# STM32H743.net
KiCad netlist of a schematic drawn in Altium Designer
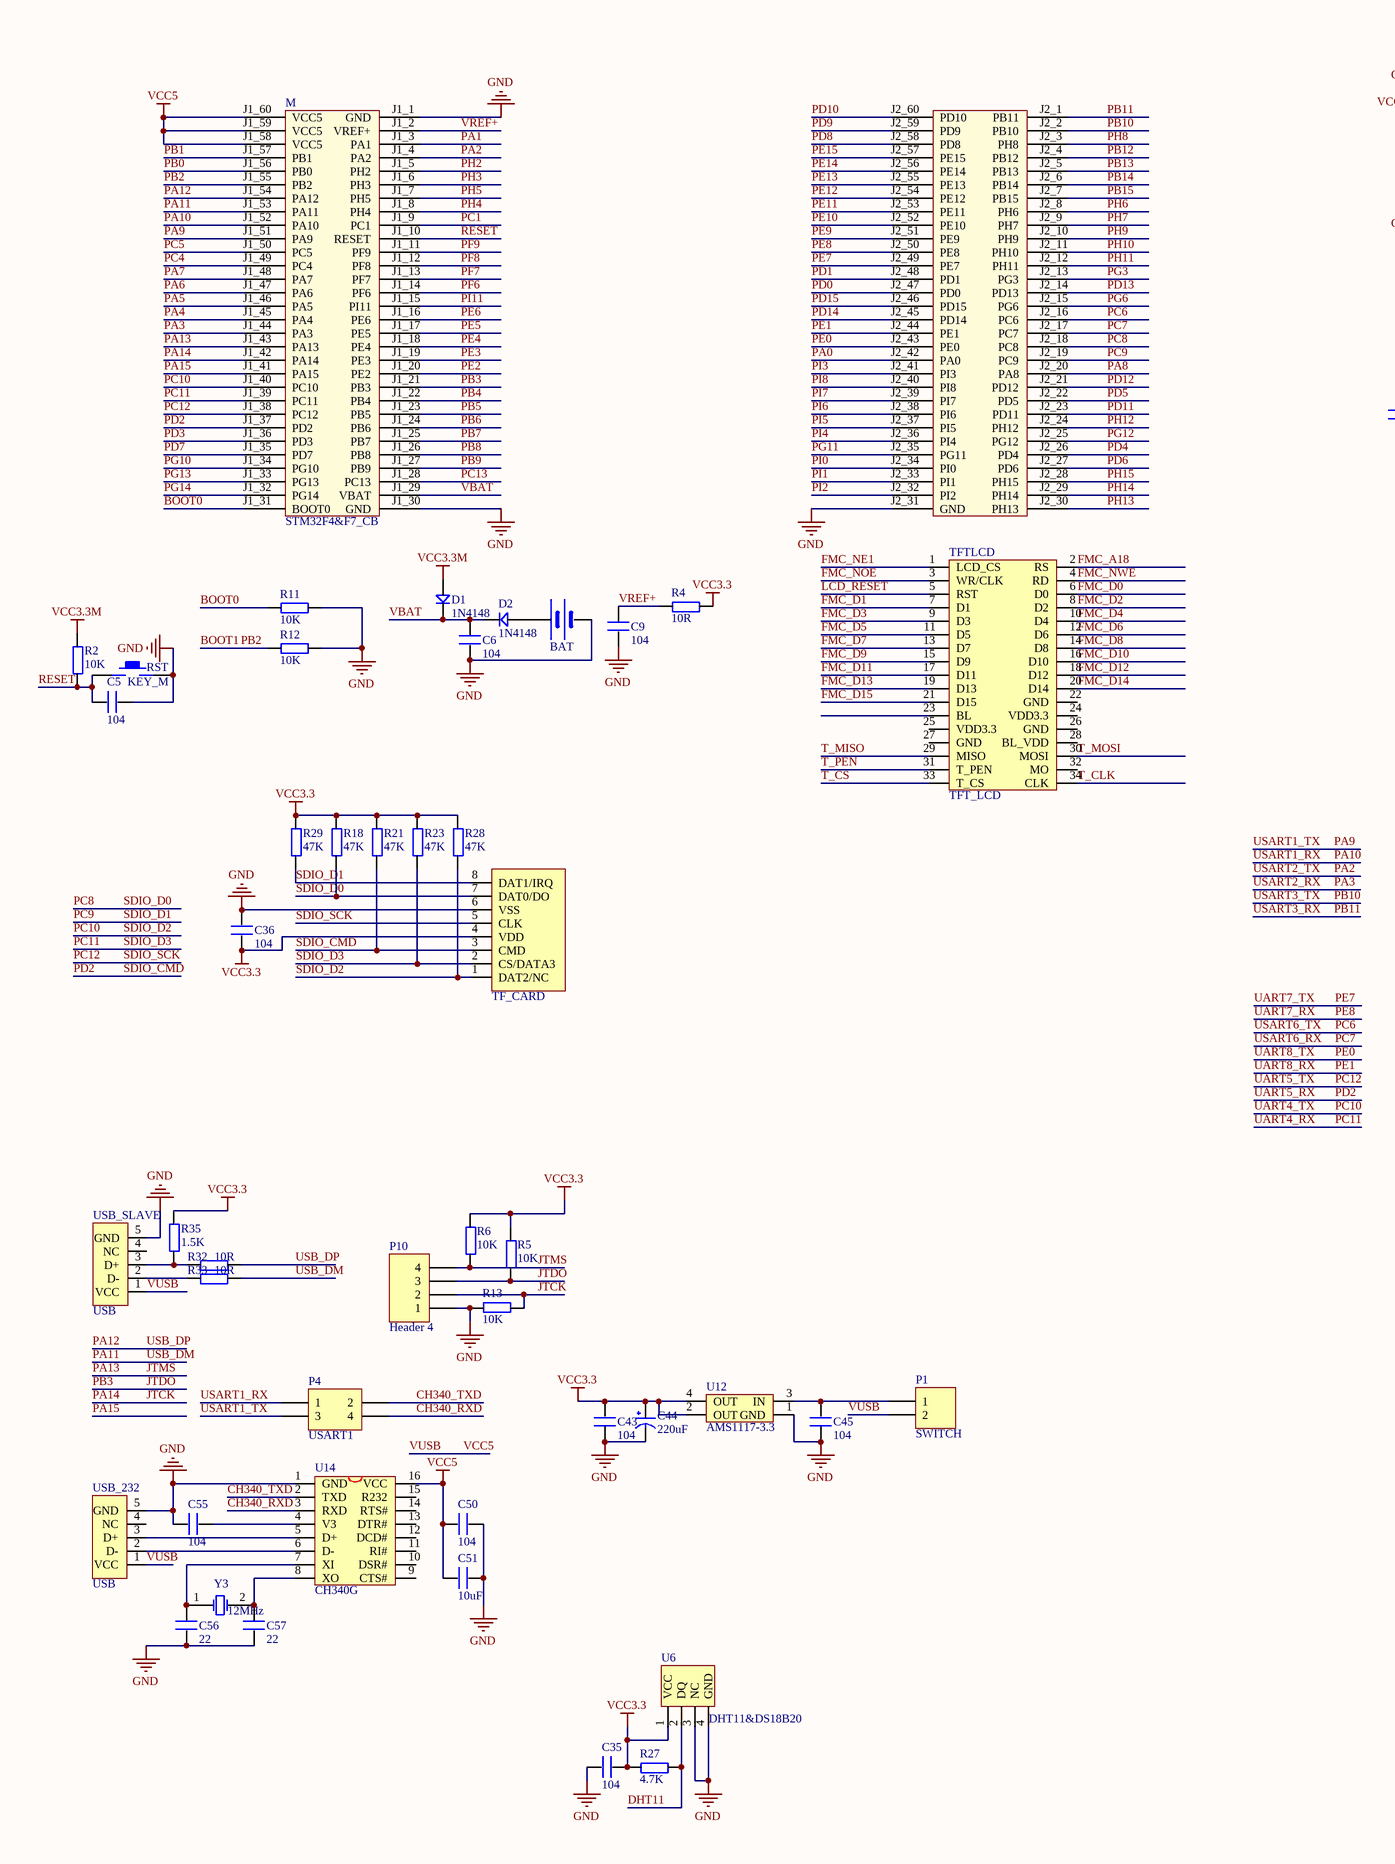
[diagram p0: STM32H743.SchDoc, left]
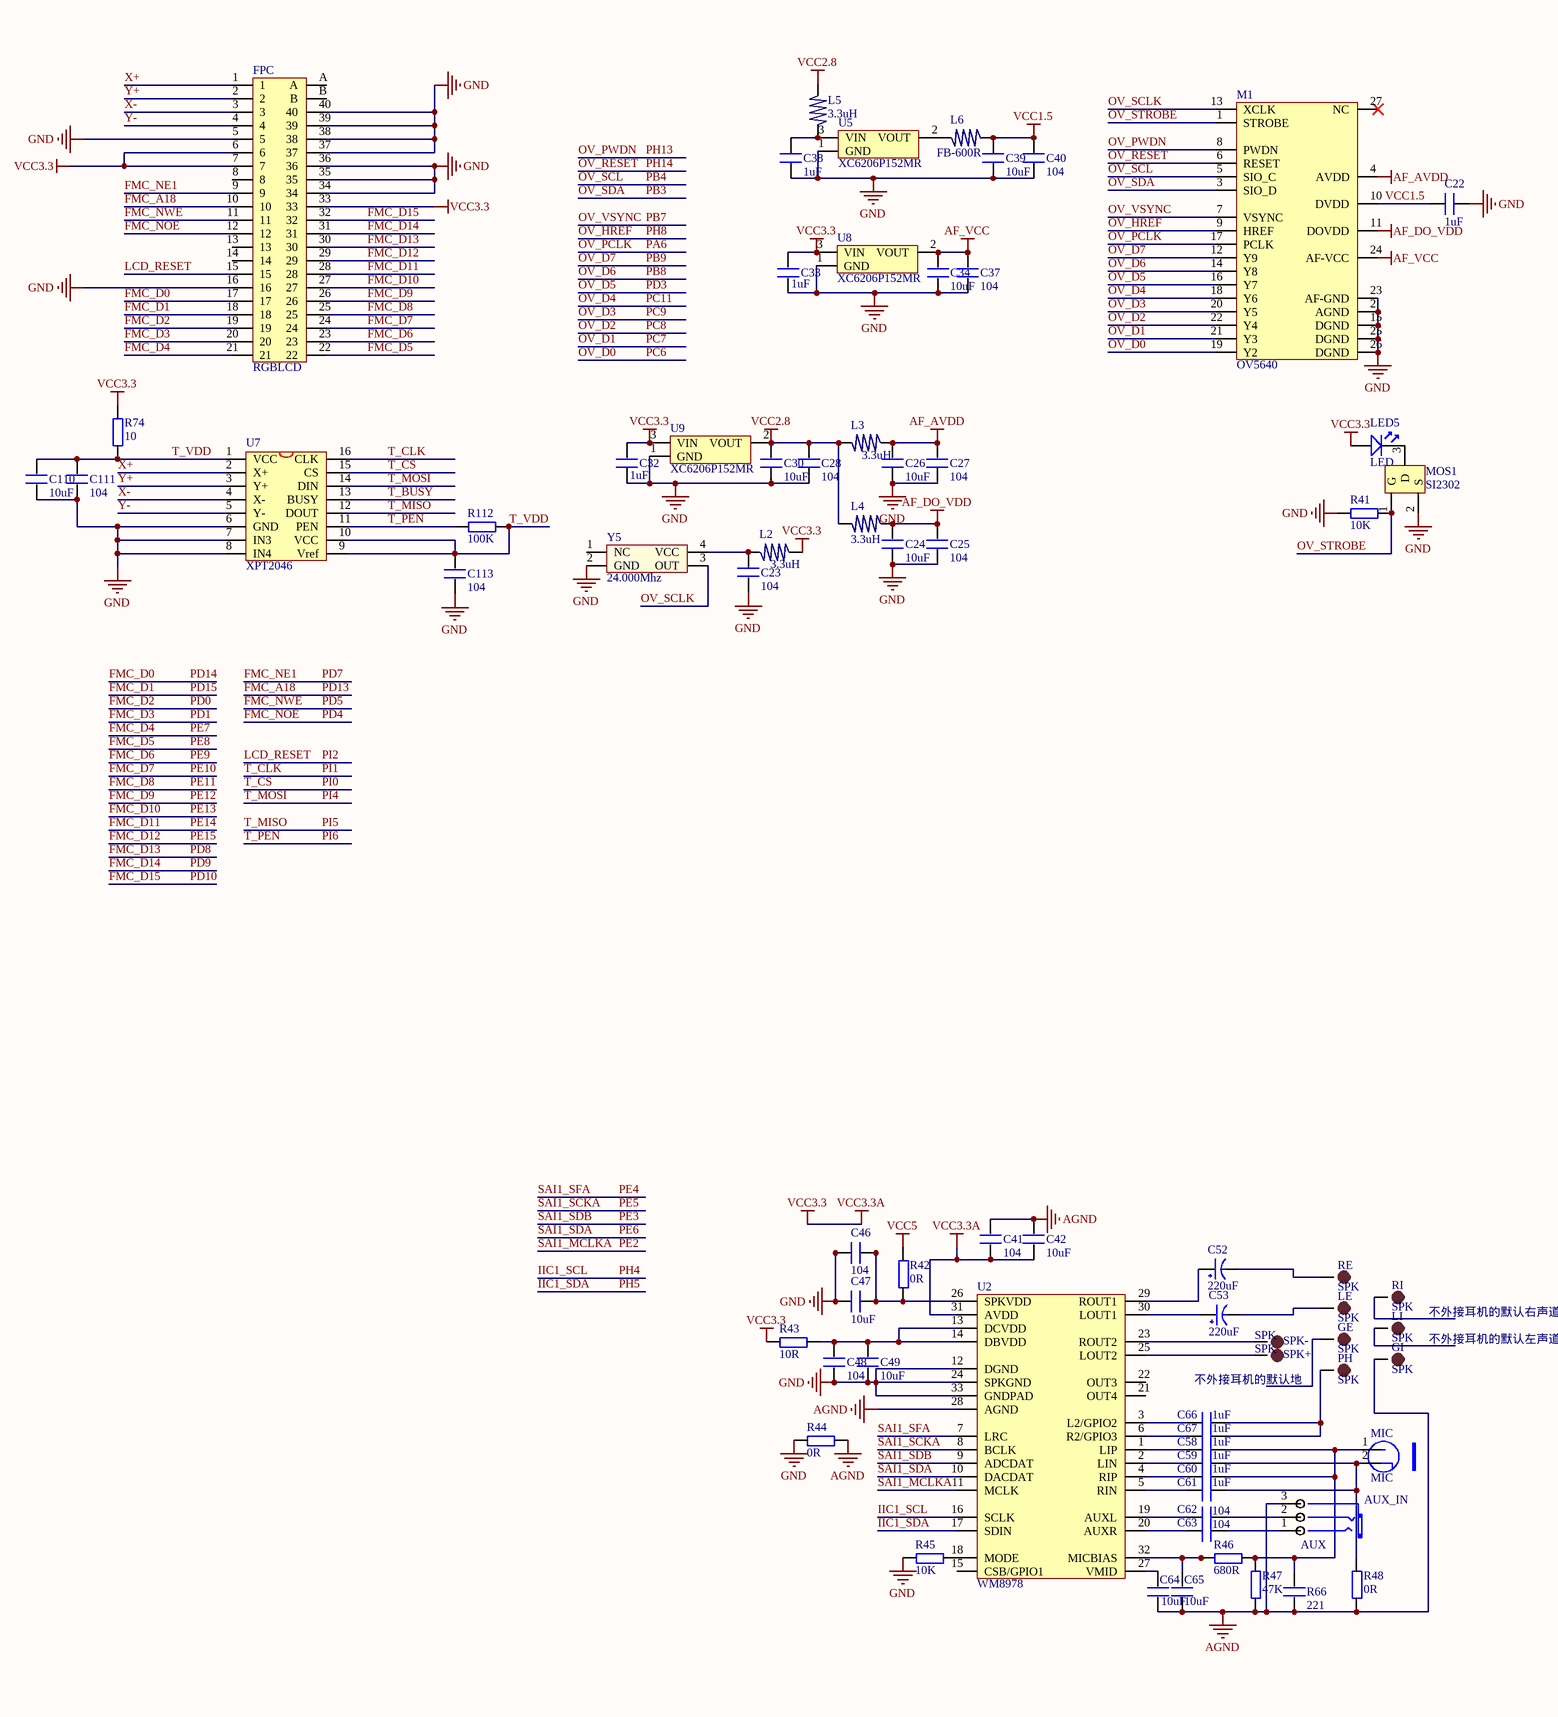
[diagram p1: STM32H743.SchDoc, right]

(export (version "E")
  (design (tool "Eeschema 10.0.6"))
  (components
    (comp (ref "AUX_IN")
      (value "AUX")
      (footprint "PHONE_ST")
      (libsource (lib "阿波罗STM32F4&F7底板封装库") (part "PHONE_M"))
    )
    (comp (ref "BAT")
      (value "BATT")
      (footprint "CR1220_A")
      (libsource (lib "WarShip V3 STM32103封装库") (part "BAT"))
    )
    (comp (ref "C5")
      (value "104")
      (footprint "C 0603_M")
      (libsource (lib "WarShip V3 STM32103封装库") (part "C"))
    )
    (comp (ref "C6")
      (value "104")
      (footprint "C 0603_M")
      (libsource (lib "WarShip V3 STM32103封装库") (part "C"))
    )
    (comp (ref "C9")
      (value "104")
      (footprint "C 0603_M")
      (libsource (lib "WarShip V3 STM32103封装库") (part "C"))
    )
    (comp (ref "C22") (value "1uF") (footprint "C 0603_M") (libsource (lib "ATK-OV5640摄像头模块封装库") (part "C")))
    (comp (ref "C23") (value "104") (footprint "C 0603_M") (libsource (lib "ATK-OV5640摄像头模块封装库") (part "C")))
    (comp (ref "C24") (value "10uF") (footprint "C 0603_M") (libsource (lib "ATK-OV5640摄像头模块封装库") (part "C")))
    (comp (ref "C25") (value "104") (footprint "C 0603_M") (libsource (lib "ATK-OV5640摄像头模块封装库") (part "C")))
    (comp (ref "C26") (value "10uF") (footprint "C 0603_M") (libsource (lib "ATK-OV5640摄像头模块封装库") (part "C")))
    (comp (ref "C27") (value "104") (footprint "C 0603_M") (libsource (lib "ATK-OV5640摄像头模块封装库") (part "C")))
    (comp (ref "C28") (value "104") (footprint "C 0603_M") (libsource (lib "ATK-OV5640摄像头模块封装库") (part "C")))
    (comp (ref "C30") (value "10uF") (footprint "C 0603_M") (libsource (lib "ATK-OV5640摄像头模块封装库") (part "C")))
    (comp (ref "C32") (value "1uF") (footprint "C 0603_M") (libsource (lib "ATK-OV5640摄像头模块封装库") (part "C")))
    (comp (ref "C33") (value "1uF") (footprint "C 0603_M") (libsource (lib "ATK-OV5640摄像头模块封装库") (part "C")))
    (comp (ref "C34") (value "10uF") (footprint "C 0603_M") (libsource (lib "ATK-OV5640摄像头模块封装库") (part "C")))
    (comp (ref "C35")
      (value "104")
      (footprint "C 0603_M")
      (libsource (lib "WarShip V3 STM32103封装库") (part "C"))
    )
    (comp (ref "C36")
      (value "104")
      (footprint "C 0603_M")
      (libsource (lib "WarShip V3 STM32103封装库") (part "C"))
    )
    (comp (ref "C37") (value "104") (footprint "C 0603_M") (libsource (lib "ATK-OV5640摄像头模块封装库") (part "C")))
    (comp (ref "C38") (value "1uF") (footprint "C 0603_M") (libsource (lib "ATK-OV5640摄像头模块封装库") (part "C")))
    (comp (ref "C39") (value "10uF") (footprint "C 0603_M") (libsource (lib "ATK-OV5640摄像头模块封装库") (part "C")))
    (comp (ref "C40") (value "104") (footprint "C 0603_M") (libsource (lib "ATK-OV5640摄像头模块封装库") (part "C")))
    (comp (ref "C41") (value "104") (footprint "C 0603_M") (libsource (lib "阿波罗STM32F4&F7底板封装库") (part "C")))
    (comp (ref "C42") (value "10uF") (footprint "C 0603_M") (libsource (lib "阿波罗STM32F4&F7底板封装库") (part "C")))
    (comp (ref "C43")
      (value "104")
      (footprint "C 0603_M")
      (libsource (lib "WarShip V3 STM32103封装库") (part "C"))
    )
    (comp (ref "C44")
      (value "220uF")
      (footprint "CT 6*6 - C")
      (libsource (lib "WarShip V3 STM32103封装库") (part "CAP"))
    )
    (comp (ref "C45")
      (value "104")
      (footprint "C 0603_M")
      (libsource (lib "WarShip V3 STM32103封装库") (part "C"))
    )
    (comp (ref "C46") (value "104") (footprint "C 0603_M") (libsource (lib "阿波罗STM32F4&F7底板封装库") (part "C")))
    (comp (ref "C47") (value "10uF") (footprint "C 0603_M") (libsource (lib "阿波罗STM32F4&F7底板封装库") (part "C")))
    (comp (ref "C48") (value "104") (footprint "C 0603_M") (libsource (lib "阿波罗STM32F4&F7底板封装库") (part "C")))
    (comp (ref "C49") (value "10uF") (footprint "C 0603_M") (libsource (lib "阿波罗STM32F4&F7底板封装库") (part "C")))
    (comp (ref "C50")
      (value "104")
      (footprint "C 0603_M")
      (libsource (lib "WarShip V3 STM32103封装库") (part "C"))
    )
    (comp (ref "C51")
      (value "10uF")
      (footprint "C 0603_M")
      (libsource (lib "WarShip V3 STM32103封装库") (part "C"))
    )
    (comp (ref "C52")
      (value "220uF")
      (footprint "CT 6*6 - C")
      (libsource (lib "阿波罗STM32F4&F7底板封装库") (part "CAP"))
    )
    (comp (ref "C53")
      (value "220uF")
      (footprint "CT 6*6 - C")
      (libsource (lib "阿波罗STM32F4&F7底板封装库") (part "CAP"))
    )
    (comp (ref "C55")
      (value "104")
      (footprint "C 0603_M")
      (libsource (lib "WarShip V3 STM32103封装库") (part "C"))
    )
    (comp (ref "C56")
      (value "22")
      (footprint "C 0603_M")
      (libsource (lib "WarShip V3 STM32103封装库") (part "C"))
    )
    (comp (ref "C57")
      (value "22")
      (footprint "C 0603_M")
      (libsource (lib "WarShip V3 STM32103封装库") (part "C"))
    )
    (comp (ref "C58") (value "1uF") (footprint "C 0603_M") (libsource (lib "阿波罗STM32F4&F7底板封装库") (part "C")))
    (comp (ref "C59") (value "1uF") (footprint "C 0603_M") (libsource (lib "阿波罗STM32F4&F7底板封装库") (part "C")))
    (comp (ref "C60") (value "1uF") (footprint "C 0603_M") (libsource (lib "阿波罗STM32F4&F7底板封装库") (part "C")))
    (comp (ref "C61") (value "1uF") (footprint "C 0603_M") (libsource (lib "阿波罗STM32F4&F7底板封装库") (part "C")))
    (comp (ref "C62") (value "104") (footprint "C 0603_M") (libsource (lib "阿波罗STM32F4&F7底板封装库") (part "C")))
    (comp (ref "C63") (value "104") (footprint "C 0603_M") (libsource (lib "阿波罗STM32F4&F7底板封装库") (part "C")))
    (comp (ref "C64") (value "10uF") (footprint "C 0603_M") (libsource (lib "阿波罗STM32F4&F7底板封装库") (part "C")))
    (comp (ref "C65") (value "10uF") (footprint "C 0603_M") (libsource (lib "阿波罗STM32F4&F7底板封装库") (part "C")))
    (comp (ref "C66") (value "1uF") (footprint "C 0603_M") (libsource (lib "阿波罗STM32F4&F7底板封装库") (part "C")))
    (comp (ref "C67") (value "1uF") (footprint "C 0603_M") (libsource (lib "阿波罗STM32F4&F7底板封装库") (part "C")))
    (comp (ref "C110") (value "10uF") (footprint "C 0603_M") (libsource (lib "3.5TFTLCD封装库") (part "C")))
    (comp (ref "C111") (value "104") (footprint "C 0603_M") (libsource (lib "3.5TFTLCD封装库") (part "C")))
    (comp (ref "C113") (value "104") (footprint "C 0603_M") (libsource (lib "3.5TFTLCD封装库") (part "C")))
    (comp (ref "D1")
      (value "1N4148")
      (footprint "DIODE_SOP")
      (libsource (lib "WarShip V3 STM32103封装库") (part "D"))
    )
    (comp (ref "D2")
      (value "1N4148")
      (footprint "DIODE_SOP")
      (libsource (lib "WarShip V3 STM32103封装库") (part "D"))
    )
    (comp (ref "FPC")
      (value "RGBLCD")
      (footprint "FPC-TOP40")
      (description "FPC-40P-0.5mm")
      (libsource (lib "STM32F429核心板封装库") (part "FPC-40"))
    )
    (comp (ref "GE")
      (value "SPK")
      (footprint "TP-1.5")
      (description "测试点")
      (libsource (lib "STM32F429核心板封装库") (part "TEST-POINT"))
    )
    (comp (ref "GI")
      (value "SPK")
      (footprint "TP-1.5")
      (description "测试点")
      (libsource (lib "STM32F429核心板封装库") (part "TEST-POINT"))
    )
    (comp (ref "L2") (value "3.3uH") (footprint "L 0603") (libsource (lib "ATK-OV5640摄像头模块封装库") (part "L")))
    (comp (ref "L3") (value "3.3uH") (footprint "L 0603") (libsource (lib "") (part "L_1")))
    (comp (ref "L4") (value "3.3uH") (footprint "L 0603") (libsource (lib "") (part "L_1")))
    (comp (ref "L5") (value "3.3uH") (footprint "L 0603") (libsource (lib "") (part "L_2")))
    (comp (ref "L6") (value "FB-600R") (footprint "L 0603") (libsource (lib "ATK-OV5640摄像头模块封装库") (part "L")))
    (comp (ref "LE")
      (value "SPK")
      (footprint "TP-1.5")
      (description "测试点")
      (libsource (lib "STM32F429核心板封装库") (part "TEST-POINT"))
    )
    (comp (ref "LED5")
      (value "LED")
      (footprint "LED 0805R")
      (libsource (lib "ATK-OV5640摄像头模块封装库") (part "LED"))
    )
    (comp (ref "LI")
      (value "SPK")
      (footprint "TP-1.5")
      (description "测试点")
      (libsource (lib "STM32F429核心板封装库") (part "TEST-POINT"))
    )
    (comp (ref "M")
      (value "STM32F4&F7_CB")
      (footprint "STM32F4&F7_CB")
      (description "F429/746 Core Board")
      (libsource (lib "阿波罗STM32F4&F7底板封装库") (part "STM32F4&F7_CB"))
    )
    (comp (ref "M1")
      (value "OV5640")
      (footprint "OV5640-24")
      (description "OV5640模组,AF,FPC")
      (libsource (lib "ATK-OV5640摄像头模块封装库") (part "OV5640"))
    )
    (comp (ref "MIC")
      (value "MIC")
      (footprint "MIC-6022")
      (libsource (lib "阿波罗STM32F4&F7底板封装库") (part "MIC"))
    )
    (comp (ref "MOS1")
      (value "SI2302")
      (footprint "SOT23-3M")
      (description "AP2306")
      (libsource (lib "ATK-OV5640摄像头模块封装库") (part "MOS-N"))
    )
    (comp (ref "P1")
      (value "SWITCH")
      (footprint "HDR2.54-LI-2P")
      (description "Header, 2-Pin")
      (fields (field (name "PUBLISHER") "Altium Limited"))
      (libsource (lib "WarShip V3 STM32103封装库") (part "Header 2"))
    )
    (comp (ref "P4")
      (value "USART1")
      (footprint "HDR2.54-LI-2x2P")
      (description "Header, 2-Pin, Dual row")
      (fields (field (name "PUBLISHER") "Altium Limited"))
      (libsource (lib "WarShip V3 STM32103封装库") (part "Header 2X2"))
    )
    (comp (ref "P10")
      (value "Header 4")
      (footprint "HDR2.54-LI-4P")
      (description "Header, 4-Pin")
      (fields (field (name "PUBLISHER") "Altium Limited"))
      (libsource (lib "WarShip V3 STM32103封装库") (part "Header 4"))
    )
    (comp (ref "PH")
      (value "SPK")
      (footprint "TP-1.5")
      (description "测试点")
      (libsource (lib "STM32F429核心板封装库") (part "TEST-POINT"))
    )
    (comp (ref "R2")
      (value "10K")
      (footprint "R 0603_M")
      (libsource (lib "WarShip V3 STM32103封装库") (part "R"))
    )
    (comp (ref "R4")
      (value "10R")
      (footprint "R 0603_M")
      (libsource (lib "WarShip V3 STM32103封装库") (part "R"))
    )
    (comp (ref "R5")
      (value "10K")
      (footprint "R 0603_M")
      (libsource (lib "WarShip V3 STM32103封装库") (part "R"))
    )
    (comp (ref "R6")
      (value "10K")
      (footprint "R 0603_M")
      (libsource (lib "WarShip V3 STM32103封装库") (part "R"))
    )
    (comp (ref "R11")
      (value "10K")
      (footprint "R 0603_M")
      (libsource (lib "WarShip V3 STM32103封装库") (part "R"))
    )
    (comp (ref "R12")
      (value "10K")
      (footprint "R 0603_M")
      (libsource (lib "WarShip V3 STM32103封装库") (part "R"))
    )
    (comp (ref "R13")
      (value "10K")
      (footprint "R 0603_M")
      (libsource (lib "WarShip V3 STM32103封装库") (part "R"))
    )
    (comp (ref "R18")
      (value "47K")
      (footprint "R 0603_M")
      (libsource (lib "WarShip V3 STM32103封装库") (part "R"))
    )
    (comp (ref "R21")
      (value "47K")
      (footprint "R 0603_M")
      (libsource (lib "WarShip V3 STM32103封装库") (part "R"))
    )
    (comp (ref "R23")
      (value "47K")
      (footprint "R 0603_M")
      (libsource (lib "WarShip V3 STM32103封装库") (part "R"))
    )
    (comp (ref "R27")
      (value "4.7K")
      (footprint "R 0603_M")
      (libsource (lib "WarShip V3 STM32103封装库") (part "R"))
    )
    (comp (ref "R28")
      (value "47K")
      (footprint "R 0603_M")
      (libsource (lib "WarShip V3 STM32103封装库") (part "R"))
    )
    (comp (ref "R29")
      (value "47K")
      (footprint "R 0603_M")
      (libsource (lib "WarShip V3 STM32103封装库") (part "R"))
    )
    (comp (ref "R32")
      (value "10R")
      (footprint "R 0603_M")
      (libsource (lib "WarShip V3 STM32103封装库") (part "R"))
    )
    (comp (ref "R33")
      (value "10R")
      (footprint "R 0603_M")
      (libsource (lib "WarShip V3 STM32103封装库") (part "R"))
    )
    (comp (ref "R35")
      (value "1.5K")
      (footprint "R 0603_M")
      (libsource (lib "WarShip V3 STM32103封装库") (part "R"))
    )
    (comp (ref "R41") (value "10K") (footprint "R 0603_M") (libsource (lib "ATK-OV5640摄像头模块封装库") (part "R")))
    (comp (ref "R42") (value "0R") (footprint "R 0603_M") (libsource (lib "阿波罗STM32F4&F7底板封装库") (part "R")))
    (comp (ref "R43") (value "10R") (footprint "R 0603_M") (libsource (lib "阿波罗STM32F4&F7底板封装库") (part "R")))
    (comp (ref "R44") (value "0R") (footprint "R 0603_M") (libsource (lib "阿波罗STM32F4&F7底板封装库") (part "R")))
    (comp (ref "R45") (value "10K") (footprint "R 0603_M") (libsource (lib "阿波罗STM32F4&F7底板封装库") (part "R")))
    (comp (ref "R46") (value "680R") (footprint "R 0603_M") (libsource (lib "阿波罗STM32F4&F7底板封装库") (part "R")))
    (comp (ref "R47") (value "47K") (footprint "R 0603_M") (libsource (lib "阿波罗STM32F4&F7底板封装库") (part "R")))
    (comp (ref "R48") (value "0R") (footprint "R 0603_M") (libsource (lib "阿波罗STM32F4&F7底板封装库") (part "R")))
    (comp (ref "R66") (value "221") (footprint "C 0603_M") (libsource (lib "阿波罗STM32F4&F7底板封装库") (part "C")))
    (comp (ref "R74") (value "10") (footprint "R 0603_M") (libsource (lib "3.5TFTLCD封装库") (part "R")))
    (comp (ref "R112") (value "100K") (footprint "R 0603_M") (libsource (lib "3.5TFTLCD封装库") (part "R")))
    (comp (ref "RE")
      (value "SPK")
      (footprint "TP-1.5")
      (description "测试点")
      (libsource (lib "STM32F429核心板封装库") (part "TEST-POINT"))
    )
    (comp (ref "RI")
      (value "SPK")
      (footprint "TP-1.5")
      (description "测试点")
      (libsource (lib "STM32F429核心板封装库") (part "TEST-POINT"))
    )
    (comp (ref "RST")
      (value "KEY_M")
      (footprint "TSW SMD-3*6*2.5")
      (libsource (lib "STM32F429核心板封装库") (part "KEY_M"))
    )
    (comp (ref "SPK+")
      (value "SPK")
      (footprint "TP-1.5")
      (description "测试点")
      (libsource (lib "STM32F429核心板封装库") (part "TEST-POINT"))
    )
    (comp (ref "SPK-")
      (value "SPK")
      (footprint "TP-1.5")
      (description "测试点")
      (libsource (lib "STM32F429核心板封装库") (part "TEST-POINT"))
    )
    (comp (ref "TFTLCD")
      (value "TFT_LCD")
      (footprint "DB2*17-3.5")
      (libsource (lib "阿波罗STM32F4&F7底板封装库") (part "TFT_LCD"))
    )
    (comp (ref "TF_CARD")
      (value "SD-MICRO-TF")
      (footprint "SD-MICRO-TF")
      (description "SD,MICRO,TF")
      (libsource (lib "Pandora_STM32L4_Board_V2.4") (part "SD-MICRO-TF"))
    )
    (comp (ref "U2")
      (value "WM8978")
      (footprint "qfn32")
      (description "24bit ADC&DAC")
      (libsource (lib "阿波罗STM32F4&F7底板封装库") (part "WM8978"))
    )
    (comp (ref "U5")
      (value "XC6206P152MR")
      (footprint "SOT23-3M")
      (description "LDO,SOT23,1.2~5.0V")
      (libsource (lib "ATK-OV5640摄像头模块封装库") (part "XC6206"))
    )
    (comp (ref "U6")
      (value "DHT11&DS18B20")
      (footprint "DHT11")
      (description "数字温湿度传感器")
      (libsource (lib "WarShip V3 STM32103封装库") (part "DHT11"))
    )
    (comp (ref "U7")
      (value "XPT2046")
      (footprint "SSOP16_M")
      (libsource (lib "3.5TFTLCD封装库") (part "ADS7843"))
    )
    (comp (ref "U8")
      (value "XC6206P152MR")
      (footprint "SOT23-3M")
      (description "LDO,SOT23,1.2~5.0V")
      (libsource (lib "ATK-OV5640摄像头模块封装库") (part "XC6206"))
    )
    (comp (ref "U9")
      (value "XC6206P152MR")
      (footprint "SOT23-3M")
      (description "LDO,SOT23,1.2~5.0V")
      (libsource (lib "ATK-OV5640摄像头模块封装库") (part "XC6206"))
    )
    (comp (ref "U12")
      (value "AMS1117-3.3")
      (footprint "AMS1117")
      (libsource (lib "WarShip V3 STM32103封装库") (part "AMS1117"))
    )
    (comp (ref "U14")
      (value "CH340G")
      (footprint "SOP16_M")
      (description "USB2UART")
      (libsource (lib "WarShip V3 STM32103封装库") (part "CH340G"))
    )
    (comp (ref "USB_232")
      (value "USB")
      (footprint "USB-MINI-A")
      (libsource (lib "WarShip V3 STM32103封装库") (part "USB5"))
    )
    (comp (ref "USB_SLAVE")
      (value "USB")
      (footprint "USB-MINI-A")
      (libsource (lib "WarShip V3 STM32103封装库") (part "USB5"))
    )
    (comp (ref "Y3")
      (value "12MHz")
      (footprint "OSC HC-49S")
      (description "Crystal Oscillator")
      (fields (field (name "PUBLISHER") "Altium Limited"))
      (libsource (lib "WarShip V3 STM32103封装库") (part "XTAL"))
    )
    (comp (ref "Y5")
      (value "24.000Mhz")
      (footprint "OSC 3225-4P")
      (description "有源晶振")
      (libsource (lib "ATK-OV5640摄像头模块封装库") (part "XTAL_S"))
    )
  )
  (nets
    (net (code "1") (name "/BOOT0") (class "Default")
      (node (ref "M") (pin "J1_31") (pinfunction "BOOT0_J1_31") (pintype "passive"))
      (node (ref "R11") (pin "1") (pintype "passive"))
    )
    (net (code "2") (name "/BOOT1") (class "Default")
      (node (ref "M") (pin "J1_55") (pinfunction "PB2_J1_55") (pintype "passive"))
      (node (ref "R12") (pin "1") (pintype "passive"))
    )
    (net (code "3") (name "/CH340_RXD") (class "Default")
      (node (ref "P4") (pin "4") (pinfunction "4_4") (pintype "passive"))
      (node (ref "U14") (pin "3") (pinfunction "RXD_3") (pintype "passive"))
    )
    (net (code "4") (name "/CH340_TXD") (class "Default")
      (node (ref "P4") (pin "2") (pinfunction "2_2") (pintype "passive"))
      (node (ref "U14") (pin "2") (pinfunction "TXD_2") (pintype "passive"))
    )
    (net (code "5") (name "/DHT11") (class "Default")
      (node (ref "R27") (pin "2") (pintype "passive"))
      (node (ref "U6") (pin "2") (pinfunction "DQ_2") (pintype "passive"))
    )
    (net (code "6") (name "/FMC_A18") (class "Default")
      (node (ref "FPC") (pin "10") (pinfunction "10_10") (pintype "passive"))
      (node (ref "M") (pin "J2_14") (pinfunction "PD13_J2_14") (pintype "passive"))
      (node (ref "TFTLCD") (pin "2") (pinfunction "RS_2") (pintype "passive"))
    )
    (net (code "7") (name "/FMC_D0") (class "Default")
      (node (ref "FPC") (pin "17") (pinfunction "17_17") (pintype "passive"))
      (node (ref "M") (pin "J2_45") (pinfunction "PD14_J2_45") (pintype "passive"))
      (node (ref "TFTLCD") (pin "6") (pinfunction "D0_6") (pintype "passive"))
    )
    (net (code "8") (name "/FMC_D1") (class "Default")
      (node (ref "FPC") (pin "18") (pinfunction "18_18") (pintype "passive"))
      (node (ref "M") (pin "J2_46") (pinfunction "PD15_J2_46") (pintype "passive"))
      (node (ref "TFTLCD") (pin "7") (pinfunction "D1_7") (pintype "passive"))
    )
    (net (code "9") (name "/FMC_D2") (class "Default")
      (node (ref "FPC") (pin "19") (pinfunction "19_19") (pintype "passive"))
      (node (ref "M") (pin "J2_47") (pinfunction "PD0_J2_47") (pintype "passive"))
      (node (ref "TFTLCD") (pin "8") (pinfunction "D2_8") (pintype "passive"))
    )
    (net (code "10") (name "/FMC_D3") (class "Default")
      (node (ref "FPC") (pin "20") (pinfunction "20_20") (pintype "passive"))
      (node (ref "M") (pin "J2_48") (pinfunction "PD1_J2_48") (pintype "passive"))
      (node (ref "TFTLCD") (pin "9") (pinfunction "D3_9") (pintype "passive"))
    )
    (net (code "11") (name "/FMC_D4") (class "Default")
      (node (ref "FPC") (pin "21") (pinfunction "21_21") (pintype "passive"))
      (node (ref "M") (pin "J2_49") (pinfunction "PE7_J2_49") (pintype "passive"))
      (node (ref "TFTLCD") (pin "10") (pinfunction "D4_10") (pintype "passive"))
    )
    (net (code "12") (name "/FMC_D5") (class "Default")
      (node (ref "FPC") (pin "22") (pinfunction "22_22") (pintype "passive"))
      (node (ref "M") (pin "J2_50") (pinfunction "PE8_J2_50") (pintype "passive"))
      (node (ref "TFTLCD") (pin "11") (pinfunction "D5_11") (pintype "passive"))
    )
    (net (code "13") (name "/FMC_D6") (class "Default")
      (node (ref "FPC") (pin "23") (pinfunction "23_23") (pintype "passive"))
      (node (ref "M") (pin "J2_51") (pinfunction "PE9_J2_51") (pintype "passive"))
      (node (ref "TFTLCD") (pin "12") (pinfunction "D6_12") (pintype "passive"))
    )
    (net (code "14") (name "/FMC_D7") (class "Default")
      (node (ref "FPC") (pin "24") (pinfunction "24_24") (pintype "passive"))
      (node (ref "M") (pin "J2_52") (pinfunction "PE10_J2_52") (pintype "passive"))
      (node (ref "TFTLCD") (pin "13") (pinfunction "D7_13") (pintype "passive"))
    )
    (net (code "15") (name "/FMC_D8") (class "Default")
      (node (ref "FPC") (pin "25") (pinfunction "25_25") (pintype "passive"))
      (node (ref "M") (pin "J2_53") (pinfunction "PE11_J2_53") (pintype "passive"))
      (node (ref "TFTLCD") (pin "14") (pinfunction "D8_14") (pintype "passive"))
    )
    (net (code "16") (name "/FMC_D9") (class "Default")
      (node (ref "FPC") (pin "26") (pinfunction "26_26") (pintype "passive"))
      (node (ref "M") (pin "J2_54") (pinfunction "PE12_J2_54") (pintype "passive"))
      (node (ref "TFTLCD") (pin "15") (pinfunction "D9_15") (pintype "passive"))
    )
    (net (code "17") (name "/FMC_D10") (class "Default")
      (node (ref "FPC") (pin "27") (pinfunction "27_27") (pintype "passive"))
      (node (ref "M") (pin "J2_55") (pinfunction "PE13_J2_55") (pintype "passive"))
      (node (ref "TFTLCD") (pin "16") (pinfunction "D10_16") (pintype "passive"))
    )
    (net (code "18") (name "/FMC_D11") (class "Default")
      (node (ref "FPC") (pin "28") (pinfunction "28_28") (pintype "passive"))
      (node (ref "M") (pin "J2_56") (pinfunction "PE14_J2_56") (pintype "passive"))
      (node (ref "TFTLCD") (pin "17") (pinfunction "D11_17") (pintype "passive"))
    )
    (net (code "19") (name "/FMC_D12") (class "Default")
      (node (ref "FPC") (pin "29") (pinfunction "29_29") (pintype "passive"))
      (node (ref "M") (pin "J2_57") (pinfunction "PE15_J2_57") (pintype "passive"))
      (node (ref "TFTLCD") (pin "18") (pinfunction "D12_18") (pintype "passive"))
    )
    (net (code "20") (name "/FMC_D13") (class "Default")
      (node (ref "FPC") (pin "30") (pinfunction "30_30") (pintype "passive"))
      (node (ref "M") (pin "J2_58") (pinfunction "PD8_J2_58") (pintype "passive"))
      (node (ref "TFTLCD") (pin "19") (pinfunction "D13_19") (pintype "passive"))
    )
    (net (code "21") (name "/FMC_D14") (class "Default")
      (node (ref "FPC") (pin "31") (pinfunction "31_31") (pintype "passive"))
      (node (ref "M") (pin "J2_59") (pinfunction "PD9_J2_59") (pintype "passive"))
      (node (ref "TFTLCD") (pin "20") (pinfunction "D14_20") (pintype "passive"))
    )
    (net (code "22") (name "/FMC_D15") (class "Default")
      (node (ref "FPC") (pin "32") (pinfunction "32_32") (pintype "passive"))
      (node (ref "M") (pin "J2_60") (pinfunction "PD10_J2_60") (pintype "passive"))
      (node (ref "TFTLCD") (pin "21") (pinfunction "D15_21") (pintype "passive"))
    )
    (net (code "23") (name "/FMC_NE1") (class "Default")
      (node (ref "FPC") (pin "9") (pinfunction "9_9") (pintype "passive"))
      (node (ref "M") (pin "J1_35") (pinfunction "PD7_J1_35") (pintype "passive"))
      (node (ref "TFTLCD") (pin "1") (pinfunction "LCD_CS_1") (pintype "passive"))
    )
    (net (code "24") (name "/FMC_NOE") (class "Default")
      (node (ref "FPC") (pin "12") (pinfunction "12_12") (pintype "passive"))
      (node (ref "M") (pin "J2_26") (pinfunction "PD4_J2_26") (pintype "passive"))
      (node (ref "TFTLCD") (pin "3") (pinfunction "WR/CLK_3") (pintype "passive"))
    )
    (net (code "25") (name "/FMC_NWE") (class "Default")
      (node (ref "FPC") (pin "11") (pinfunction "11_11") (pintype "passive"))
      (node (ref "M") (pin "J2_22") (pinfunction "PD5_J2_22") (pintype "passive"))
      (node (ref "TFTLCD") (pin "4") (pinfunction "RD_4") (pintype "passive"))
    )
    (net (code "26") (name "/IIC1_SCL") (class "Default")
      (node (ref "M") (pin "J1_8") (pinfunction "PH4_J1_8") (pintype "passive"))
      (node (ref "U2") (pin "16") (pinfunction "SCLK_16") (pintype "passive"))
    )
    (net (code "27") (name "/IIC1_SDA") (class "Default")
      (node (ref "M") (pin "J1_7") (pinfunction "PH5_J1_7") (pintype "passive"))
      (node (ref "U2") (pin "17") (pinfunction "SDIN_17") (pintype "passive"))
    )
    (net (code "28") (name "/JTCK") (class "Default")
      (node (ref "M") (pin "J1_42") (pinfunction "PA14_J1_42") (pintype "passive"))
      (node (ref "P10") (pin "2") (pinfunction "2_2") (pintype "passive"))
      (node (ref "R13") (pin "1") (pintype "passive"))
    )
    (net (code "29") (name "/JTDO") (class "Default")
      (node (ref "M") (pin "J1_21") (pinfunction "PB3_J1_21") (pintype "passive"))
      (node (ref "M1") (pin "3") (pinfunction "SIO_D_3") (pintype "passive"))
      (node (ref "P10") (pin "3") (pinfunction "3_3") (pintype "passive"))
      (node (ref "R5") (pin "1") (pintype "passive"))
    )
    (net (code "30") (name "/JTMS") (class "Default")
      (node (ref "M") (pin "J1_43") (pinfunction "PA13_J1_43") (pintype "passive"))
      (node (ref "P10") (pin "4") (pinfunction "4_4") (pintype "passive"))
      (node (ref "R6") (pin "1") (pintype "passive"))
    )
    (net (code "31") (name "/LCD_RESET") (class "Default")
      (node (ref "FPC") (pin "15") (pinfunction "15_15") (pintype "passive"))
      (node (ref "M") (pin "J2_32") (pinfunction "PI2_J2_32") (pintype "passive"))
      (node (ref "TFTLCD") (pin "5") (pinfunction "RST_5") (pintype "passive"))
    )
    (net (code "32") (name "/OV_D0") (class "Default")
      (node (ref "M") (pin "J2_16") (pinfunction "PC6_J2_16") (pintype "passive"))
      (node (ref "M1") (pin "19") (pinfunction "Y2_19") (pintype "passive"))
    )
    (net (code "33") (name "/OV_D1") (class "Default")
      (node (ref "M") (pin "J2_17") (pinfunction "PC7_J2_17") (pintype "passive"))
      (node (ref "M1") (pin "21") (pinfunction "Y3_21") (pintype "passive"))
    )
    (net (code "34") (name "/OV_D2") (class "Default")
      (node (ref "M") (pin "J2_18") (pinfunction "PC8_J2_18") (pintype "passive"))
      (node (ref "M1") (pin "22") (pinfunction "Y4_22") (pintype "passive"))
      (node (ref "R18") (pin "1") (pintype "passive"))
      (node (ref "TF_CARD") (pin "7") (pinfunction "DAT0/DO_7") (pintype "passive"))
    )
    (net (code "35") (name "/OV_D3") (class "Default")
      (node (ref "M") (pin "J2_19") (pinfunction "PC9_J2_19") (pintype "passive"))
      (node (ref "M1") (pin "20") (pinfunction "Y5_20") (pintype "passive"))
      (node (ref "R29") (pin "1") (pintype "passive"))
      (node (ref "TF_CARD") (pin "8") (pinfunction "DAT1/IRQ_8") (pintype "passive"))
    )
    (net (code "36") (name "/OV_D4") (class "Default")
      (node (ref "M") (pin "J1_39") (pinfunction "PC11_J1_39") (pintype "passive"))
      (node (ref "M1") (pin "18") (pinfunction "Y6_18") (pintype "passive"))
      (node (ref "R23") (pin "1") (pintype "passive"))
      (node (ref "TF_CARD") (pin "2") (pinfunction "CS/DATA3_2") (pintype "passive"))
    )
    (net (code "37") (name "/OV_D5") (class "Default")
      (node (ref "M") (pin "J1_36") (pinfunction "PD3_J1_36") (pintype "passive"))
      (node (ref "M1") (pin "16") (pinfunction "Y7_16") (pintype "passive"))
    )
    (net (code "38") (name "/OV_D6") (class "Default")
      (node (ref "M") (pin "J1_26") (pinfunction "PB8_J1_26") (pintype "passive"))
      (node (ref "M1") (pin "14") (pinfunction "Y8_14") (pintype "passive"))
    )
    (net (code "39") (name "/OV_D7") (class "Default")
      (node (ref "M") (pin "J1_27") (pinfunction "PB9_J1_27") (pintype "passive"))
      (node (ref "M1") (pin "12") (pinfunction "Y9_12") (pintype "passive"))
    )
    (net (code "40") (name "/OV_HREF") (class "Default")
      (node (ref "M") (pin "J2_3") (pinfunction "PH8_J2_3") (pintype "passive"))
      (node (ref "M1") (pin "9") (pinfunction "HREF_9") (pintype "passive"))
    )
    (net (code "41") (name "/OV_PCLK") (class "Default")
      (node (ref "M") (pin "J1_47") (pinfunction "PA6_J1_47") (pintype "passive"))
      (node (ref "M1") (pin "17") (pinfunction "PCLK_17") (pintype "passive"))
    )
    (net (code "42") (name "/OV_PWDN") (class "Default")
      (node (ref "M") (pin "J2_30") (pinfunction "PH13_J2_30") (pintype "passive"))
      (node (ref "M1") (pin "8") (pinfunction "PWDN_8") (pintype "passive"))
    )
    (net (code "43") (name "/OV_RESET") (class "Default")
      (node (ref "M") (pin "J2_29") (pinfunction "PH14_J2_29") (pintype "passive"))
      (node (ref "M1") (pin "6") (pinfunction "RESET_6") (pintype "passive"))
    )
    (net (code "44") (name "/OV_SCL") (class "Default")
      (node (ref "M") (pin "J1_22") (pinfunction "PB4_J1_22") (pintype "passive"))
      (node (ref "M1") (pin "5") (pinfunction "SIO_C_5") (pintype "passive"))
    )
    (net (code "45") (name "/OV_SCLK") (class "Default")
      (node (ref "M1") (pin "13") (pinfunction "XCLK_13") (pintype "passive"))
      (node (ref "Y5") (pin "3") (pinfunction "OUT_3") (pintype "passive"))
    )
    (net (code "46") (name "/OV_STROBE") (class "Default")
      (node (ref "M1") (pin "1") (pinfunction "STROBE_1") (pintype "passive"))
      (node (ref "MOS1") (pin "1") (pinfunction "G_1") (pintype "passive"))
      (node (ref "R41") (pin "2") (pintype "passive"))
    )
    (net (code "47") (name "/OV_VSYNC") (class "Default")
      (node (ref "M") (pin "J1_25") (pinfunction "PB7_J1_25") (pintype "passive"))
      (node (ref "M1") (pin "7") (pinfunction "VSYNC_7") (pintype "passive"))
    )
    (net (code "48") (name "/PA0") (class "Default")
      (node (ref "M") (pin "J2_42") (pinfunction "PA0_J2_42") (pintype "passive"))
    )
    (net (code "49") (name "/PA1") (class "Default")
      (node (ref "M") (pin "J1_3") (pinfunction "PA1_J1_3") (pintype "passive"))
    )
    (net (code "50") (name "/PA2") (class "Default")
      (node (ref "M") (pin "J1_4") (pinfunction "PA2_J1_4") (pintype "passive"))
    )
    (net (code "51") (name "/PA3") (class "Default")
      (node (ref "M") (pin "J1_44") (pinfunction "PA3_J1_44") (pintype "passive"))
    )
    (net (code "52") (name "/PA4") (class "Default")
      (node (ref "M") (pin "J1_45") (pinfunction "PA4_J1_45") (pintype "passive"))
    )
    (net (code "53") (name "/PA5") (class "Default")
      (node (ref "M") (pin "J1_46") (pinfunction "PA5_J1_46") (pintype "passive"))
    )
    (net (code "54") (name "/PA7") (class "Default")
      (node (ref "M") (pin "J1_48") (pinfunction "PA7_J1_48") (pintype "passive"))
    )
    (net (code "55") (name "/PA8") (class "Default")
      (node (ref "M") (pin "J2_20") (pinfunction "PA8_J2_20") (pintype "passive"))
    )
    (net (code "56") (name "/PA9") (class "Default")
      (node (ref "M") (pin "J1_51") (pinfunction "PA9_J1_51") (pintype "passive"))
      (node (ref "P4") (pin "3") (pinfunction "3_3") (pintype "passive"))
    )
    (net (code "57") (name "/PA10") (class "Default")
      (node (ref "M") (pin "J1_52") (pinfunction "PA10_J1_52") (pintype "passive"))
      (node (ref "P4") (pin "1") (pinfunction "1_1") (pintype "passive"))
    )
    (net (code "58") (name "/PA11") (class "Default")
      (node (ref "M") (pin "J1_53") (pinfunction "PA11_J1_53") (pintype "passive"))
      (node (ref "R33") (pin "2") (pintype "passive"))
    )
    (net (code "59") (name "/PA12") (class "Default")
      (node (ref "M") (pin "J1_54") (pinfunction "PA12_J1_54") (pintype "passive"))
      (node (ref "R32") (pin "2") (pintype "passive"))
    )
    (net (code "60") (name "/PA15") (class "Default")
      (node (ref "M") (pin "J1_41") (pinfunction "PA15_J1_41") (pintype "passive"))
    )
    (net (code "61") (name "/PB0") (class "Default")
      (node (ref "M") (pin "J1_56") (pinfunction "PB0_J1_56") (pintype "passive"))
    )
    (net (code "62") (name "/PB1") (class "Default")
      (node (ref "M") (pin "J1_57") (pinfunction "PB1_J1_57") (pintype "passive"))
    )
    (net (code "63") (name "/PB5") (class "Default")
      (node (ref "M") (pin "J1_23") (pinfunction "PB5_J1_23") (pintype "passive"))
    )
    (net (code "64") (name "/PB6") (class "Default")
      (node (ref "M") (pin "J1_24") (pinfunction "PB6_J1_24") (pintype "passive"))
    )
    (net (code "65") (name "/PB10") (class "Default")
      (node (ref "M") (pin "J2_2") (pinfunction "PB10_J2_2") (pintype "passive"))
    )
    (net (code "66") (name "/PB11") (class "Default")
      (node (ref "M") (pin "J2_1") (pinfunction "PB11_J2_1") (pintype "passive"))
    )
    (net (code "67") (name "/PB12") (class "Default")
      (node (ref "M") (pin "J2_4") (pinfunction "PB12_J2_4") (pintype "passive"))
    )
    (net (code "68") (name "/PB13") (class "Default")
      (node (ref "M") (pin "J2_5") (pinfunction "PB13_J2_5") (pintype "passive"))
    )
    (net (code "69") (name "/PB14") (class "Default")
      (node (ref "M") (pin "J2_6") (pinfunction "PB14_J2_6") (pintype "passive"))
    )
    (net (code "70") (name "/PB15") (class "Default")
      (node (ref "M") (pin "J2_7") (pinfunction "PB15_J2_7") (pintype "passive"))
    )
    (net (code "71") (name "/PC1") (class "Default")
      (node (ref "M") (pin "J1_9") (pinfunction "PC1_J1_9") (pintype "passive"))
    )
    (net (code "72") (name "/PC4") (class "Default")
      (node (ref "M") (pin "J1_49") (pinfunction "PC4_J1_49") (pintype "passive"))
    )
    (net (code "73") (name "/PC5") (class "Default")
      (node (ref "M") (pin "J1_50") (pinfunction "PC5_J1_50") (pintype "passive"))
    )
    (net (code "74") (name "/PC10") (class "Default")
      (node (ref "M") (pin "J1_40") (pinfunction "PC10_J1_40") (pintype "passive"))
      (node (ref "R28") (pin "1") (pintype "passive"))
      (node (ref "TF_CARD") (pin "1") (pinfunction "DAT2/NC_1") (pintype "passive"))
    )
    (net (code "75") (name "/PC12") (class "Default")
      (node (ref "M") (pin "J1_38") (pinfunction "PC12_J1_38") (pintype "passive"))
      (node (ref "TF_CARD") (pin "5") (pinfunction "CLK_5") (pintype "passive"))
    )
    (net (code "76") (name "/PC13") (class "Default")
      (node (ref "M") (pin "J1_28") (pinfunction "PC13_J1_28") (pintype "passive"))
    )
    (net (code "77") (name "/PD2") (class "Default")
      (node (ref "M") (pin "J1_37") (pinfunction "PD2_J1_37") (pintype "passive"))
      (node (ref "R21") (pin "1") (pintype "passive"))
      (node (ref "TF_CARD") (pin "3") (pinfunction "CMD_3") (pintype "passive"))
    )
    (net (code "78") (name "/PD6") (class "Default")
      (node (ref "M") (pin "J2_27") (pinfunction "PD6_J2_27") (pintype "passive"))
    )
    (net (code "79") (name "/PD11") (class "Default")
      (node (ref "M") (pin "J2_23") (pinfunction "PD11_J2_23") (pintype "passive"))
    )
    (net (code "80") (name "/PD12") (class "Default")
      (node (ref "M") (pin "J2_21") (pinfunction "PD12_J2_21") (pintype "passive"))
    )
    (net (code "81") (name "/PE0") (class "Default")
      (node (ref "M") (pin "J2_43") (pinfunction "PE0_J2_43") (pintype "passive"))
    )
    (net (code "82") (name "/PE1") (class "Default")
      (node (ref "M") (pin "J2_44") (pinfunction "PE1_J2_44") (pintype "passive"))
    )
    (net (code "83") (name "/PE2") (class "Default")
      (node (ref "M") (pin "J1_20") (pinfunction "PE2_J1_20") (pintype "passive"))
      (node (ref "U2") (pin "11") (pinfunction "MCLK_11") (pintype "passive"))
    )
    (net (code "84") (name "/PE3") (class "Default")
      (node (ref "M") (pin "J1_19") (pinfunction "PE3_J1_19") (pintype "passive"))
      (node (ref "U2") (pin "9") (pinfunction "ADCDAT_9") (pintype "passive"))
    )
    (net (code "85") (name "/PE4") (class "Default")
      (node (ref "M") (pin "J1_18") (pinfunction "PE4_J1_18") (pintype "passive"))
      (node (ref "U2") (pin "7") (pinfunction "LRC_7") (pintype "passive"))
    )
    (net (code "86") (name "/PE5") (class "Default")
      (node (ref "M") (pin "J1_17") (pinfunction "PE5_J1_17") (pintype "passive"))
      (node (ref "U2") (pin "8") (pinfunction "BCLK_8") (pintype "passive"))
    )
    (net (code "87") (name "/PE6") (class "Default")
      (node (ref "M") (pin "J1_16") (pinfunction "PE6_J1_16") (pintype "passive"))
      (node (ref "U2") (pin "10") (pinfunction "DACDAT_10") (pintype "passive"))
    )
    (net (code "88") (name "/PF6") (class "Default")
      (node (ref "M") (pin "J1_14") (pinfunction "PF6_J1_14") (pintype "passive"))
    )
    (net (code "89") (name "/PF7") (class "Default")
      (node (ref "M") (pin "J1_13") (pinfunction "PF7_J1_13") (pintype "passive"))
    )
    (net (code "90") (name "/PF8") (class "Default")
      (node (ref "M") (pin "J1_12") (pinfunction "PF8_J1_12") (pintype "passive"))
    )
    (net (code "91") (name "/PF9") (class "Default")
      (node (ref "M") (pin "J1_11") (pinfunction "PF9_J1_11") (pintype "passive"))
    )
    (net (code "92") (name "/PG3") (class "Default")
      (node (ref "M") (pin "J2_13") (pinfunction "PG3_J2_13") (pintype "passive"))
    )
    (net (code "93") (name "/PG6") (class "Default")
      (node (ref "M") (pin "J2_15") (pinfunction "PG6_J2_15") (pintype "passive"))
    )
    (net (code "94") (name "/PG10") (class "Default")
      (node (ref "M") (pin "J1_34") (pinfunction "PG10_J1_34") (pintype "passive"))
    )
    (net (code "95") (name "/PG11") (class "Default")
      (node (ref "M") (pin "J2_35") (pinfunction "PG11_J2_35") (pintype "passive"))
    )
    (net (code "96") (name "/PG12") (class "Default")
      (node (ref "M") (pin "J2_25") (pinfunction "PG12_J2_25") (pintype "passive"))
    )
    (net (code "97") (name "/PG13") (class "Default")
      (node (ref "M") (pin "J1_33") (pinfunction "PG13_J1_33") (pintype "passive"))
    )
    (net (code "98") (name "/PG14") (class "Default")
      (node (ref "M") (pin "J1_32") (pinfunction "PG14_J1_32") (pintype "passive"))
    )
    (net (code "99") (name "/PH2") (class "Default")
      (node (ref "M") (pin "J1_5") (pinfunction "PH2_J1_5") (pintype "passive"))
    )
    (net (code "100") (name "/PH3") (class "Default")
      (node (ref "M") (pin "J1_6") (pinfunction "PH3_J1_6") (pintype "passive"))
    )
    (net (code "101") (name "/PH6") (class "Default")
      (node (ref "M") (pin "J2_8") (pinfunction "PH6_J2_8") (pintype "passive"))
    )
    (net (code "102") (name "/PH7") (class "Default")
      (node (ref "M") (pin "J2_9") (pinfunction "PH7_J2_9") (pintype "passive"))
    )
    (net (code "103") (name "/PH9") (class "Default")
      (node (ref "M") (pin "J2_10") (pinfunction "PH9_J2_10") (pintype "passive"))
    )
    (net (code "104") (name "/PH10") (class "Default")
      (node (ref "M") (pin "J2_11") (pinfunction "PH10_J2_11") (pintype "passive"))
    )
    (net (code "105") (name "/PH11") (class "Default")
      (node (ref "M") (pin "J2_12") (pinfunction "PH11_J2_12") (pintype "passive"))
    )
    (net (code "106") (name "/PH12") (class "Default")
      (node (ref "M") (pin "J2_24") (pinfunction "PH12_J2_24") (pintype "passive"))
    )
    (net (code "107") (name "/PH15") (class "Default")
      (node (ref "M") (pin "J2_28") (pinfunction "PH15_J2_28") (pintype "passive"))
    )
    (net (code "108") (name "/PI0") (class "Default")
      (node (ref "M") (pin "J2_34") (pinfunction "PI0_J2_34") (pintype "passive"))
      (node (ref "TFTLCD") (pin "33") (pinfunction "T_CS_33") (pintype "passive"))
      (node (ref "U7") (pin "15") (pinfunction "CS_15") (pintype "passive"))
    )
    (net (code "109") (name "/PI1") (class "Default")
      (node (ref "M") (pin "J2_33") (pinfunction "PI1_J2_33") (pintype "passive"))
      (node (ref "TFTLCD") (pin "34") (pinfunction "CLK_34") (pintype "passive"))
      (node (ref "U7") (pin "16") (pinfunction "CLK_16") (pintype "passive"))
    )
    (net (code "110") (name "/PI3") (class "Default")
      (node (ref "M") (pin "J2_41") (pinfunction "PI3_J2_41") (pintype "passive"))
    )
    (net (code "111") (name "/PI4") (class "Default")
      (node (ref "M") (pin "J2_36") (pinfunction "PI4_J2_36") (pintype "passive"))
      (node (ref "TFTLCD") (pin "30") (pinfunction "MOSI_30") (pintype "passive"))
      (node (ref "U7") (pin "14") (pinfunction "DIN_14") (pintype "passive"))
    )
    (net (code "112") (name "/PI5") (class "Default")
      (node (ref "M") (pin "J2_37") (pinfunction "PI5_J2_37") (pintype "passive"))
      (node (ref "TFTLCD") (pin "29") (pinfunction "MISO_29") (pintype "passive"))
      (node (ref "U7") (pin "12") (pinfunction "DOUT_12") (pintype "passive"))
    )
    (net (code "113") (name "/PI6") (class "Default")
      (node (ref "M") (pin "J2_38") (pinfunction "PI6_J2_38") (pintype "passive"))
      (node (ref "R112") (pin "1") (pintype "passive"))
      (node (ref "TFTLCD") (pin "31") (pinfunction "T_PEN_31") (pintype "passive"))
      (node (ref "U7") (pin "11") (pinfunction "PEN_11") (pintype "passive"))
    )
    (net (code "114") (name "/PI7") (class "Default")
      (node (ref "M") (pin "J2_39") (pinfunction "PI7_J2_39") (pintype "passive"))
    )
    (net (code "115") (name "/PI8") (class "Default")
      (node (ref "M") (pin "J2_40") (pinfunction "PI8_J2_40") (pintype "passive"))
    )
    (net (code "116") (name "/PI11") (class "Default")
      (node (ref "M") (pin "J1_15") (pinfunction "PI11_J1_15") (pintype "passive"))
    )
    (net (code "117") (name "/RESET") (class "Default")
      (node (ref "C5") (pin "2") (pintype "passive"))
      (node (ref "M") (pin "J1_10") (pinfunction "RESET_J1_10") (pintype "passive"))
      (node (ref "R2") (pin "1") (pintype "passive"))
      (node (ref "RST") (pin "1") (pinfunction "1_1") (pintype "passive"))
    )
    (net (code "118") (name "/T_BUSY") (class "Default")
      (node (ref "U7") (pin "13") (pinfunction "BUSY_13") (pintype "passive"))
    )
    (net (code "119") (name "/T_VDD") (class "Default")
      (node (ref "C110") (pin "2") (pintype "passive"))
      (node (ref "C111") (pin "2") (pintype "passive"))
      (node (ref "C113") (pin "2") (pintype "passive"))
      (node (ref "R112") (pin "2") (pintype "passive"))
      (node (ref "R74") (pin "1") (pintype "passive"))
      (node (ref "U7") (pin "1") (pinfunction "VCC_1") (pintype "passive"))
      (node (ref "U7") (pin "10") (pinfunction "VCC_10") (pintype "passive"))
      (node (ref "U7") (pin "9") (pinfunction "Vref_9") (pintype "passive"))
    )
    (net (code "120") (name "/VBAT") (class "Default")
      (node (ref "C6") (pin "2") (pintype "passive"))
      (node (ref "D1") (pin "2") (pintype "passive"))
      (node (ref "D2") (pin "2") (pintype "passive"))
      (node (ref "M") (pin "J1_29") (pinfunction "VBAT_J1_29") (pintype "passive"))
    )
    (net (code "121") (name "/VREF+") (class "Default")
      (node (ref "C9") (pin "2") (pintype "passive"))
      (node (ref "M") (pin "J1_2") (pinfunction "VREF+_J1_2") (pintype "passive"))
      (node (ref "R4") (pin "1") (pintype "passive"))
    )
    (net (code "122") (name "/X+") (class "Default")
      (node (ref "FPC") (pin "1") (pinfunction "1_1") (pintype "passive"))
      (node (ref "U7") (pin "2") (pinfunction "X+_2") (pintype "passive"))
    )
    (net (code "123") (name "/X-") (class "Default")
      (node (ref "FPC") (pin "3") (pinfunction "3_3") (pintype "passive"))
      (node (ref "U7") (pin "4") (pinfunction "X-_4") (pintype "passive"))
    )
    (net (code "124") (name "/Y+") (class "Default")
      (node (ref "FPC") (pin "2") (pinfunction "2_2") (pintype "passive"))
      (node (ref "U7") (pin "3") (pinfunction "Y+_3") (pintype "passive"))
    )
    (net (code "125") (name "/Y-") (class "Default")
      (node (ref "FPC") (pin "4") (pinfunction "4_4") (pintype "passive"))
      (node (ref "U7") (pin "5") (pinfunction "Y-_5") (pintype "passive"))
    )
    (net (code "126") (name "AF_AVDD") (class "Default")
      (node (ref "C26") (pin "2") (pintype "passive"))
      (node (ref "C27") (pin "2") (pintype "passive"))
      (node (ref "L3") (pin "1") (pintype "passive"))
      (node (ref "M1") (pin "4") (pinfunction "AVDD_4") (pintype "passive"))
    )
    (net (code "127") (name "AF_DO_VDD") (class "Default")
      (node (ref "C24") (pin "2") (pintype "passive"))
      (node (ref "C25") (pin "2") (pintype "passive"))
      (node (ref "L4") (pin "1") (pintype "passive"))
      (node (ref "M1") (pin "11") (pinfunction "DOVDD_11") (pintype "passive"))
    )
    (net (code "128") (name "AF_VCC") (class "Default")
      (node (ref "C34") (pin "2") (pintype "passive"))
      (node (ref "C37") (pin "2") (pintype "passive"))
      (node (ref "M1") (pin "24") (pinfunction "AF-VCC_24") (pintype "passive"))
      (node (ref "U8") (pin "2") (pinfunction "VOUT_2") (pintype "passive"))
    )
    (net (code "129") (name "AGND") (class "Default")
      (node (ref "AUX_IN") (pin "3") (pinfunction "COM_3") (pintype "passive"))
      (node (ref "C41") (pin "2") (pintype "passive"))
      (node (ref "C42") (pin "2") (pintype "passive"))
      (node (ref "C64") (pin "1") (pintype "passive"))
      (node (ref "C65") (pin "1") (pintype "passive"))
      (node (ref "GI") (pin "1") (pinfunction "1_1") (pintype "passive"))
      (node (ref "R44") (pin "2") (pintype "passive"))
      (node (ref "R47") (pin "1") (pintype "passive"))
      (node (ref "R48") (pin "1") (pintype "passive"))
      (node (ref "R66") (pin "1") (pintype "passive"))
      (node (ref "U2") (pin "28") (pinfunction "AGND_28") (pintype "passive"))
    )
    (net (code "130") (name "GND") (class "Default")
      (node (ref "BAT") (pin "2") (pinfunction "GND_2") (pintype "passive"))
      (node (ref "C110") (pin "1") (pintype "passive"))
      (node (ref "C111") (pin "1") (pintype "passive"))
      (node (ref "C113") (pin "1") (pintype "passive"))
      (node (ref "C22") (pin "2") (pintype "passive"))
      (node (ref "C23") (pin "1") (pintype "passive"))
      (node (ref "C24") (pin "1") (pintype "passive"))
      (node (ref "C25") (pin "1") (pintype "passive"))
      (node (ref "C26") (pin "1") (pintype "passive"))
      (node (ref "C27") (pin "1") (pintype "passive"))
      (node (ref "C28") (pin "1") (pintype "passive"))
      (node (ref "C30") (pin "1") (pintype "passive"))
      (node (ref "C32") (pin "1") (pintype "passive"))
      (node (ref "C33") (pin "1") (pintype "passive"))
      (node (ref "C34") (pin "1") (pintype "passive"))
      (node (ref "C35") (pin "1") (pintype "passive"))
      (node (ref "C36") (pin "2") (pintype "passive"))
      (node (ref "C37") (pin "1") (pintype "passive"))
      (node (ref "C38") (pin "1") (pintype "passive"))
      (node (ref "C39") (pin "1") (pintype "passive"))
      (node (ref "C40") (pin "1") (pintype "passive"))
      (node (ref "C43") (pin "1") (pintype "passive"))
      (node (ref "C44") (pin "2") (pinfunction "GND_2") (pintype "passive"))
      (node (ref "C45") (pin "1") (pintype "passive"))
      (node (ref "C46") (pin "1") (pintype "passive"))
      (node (ref "C47") (pin "1") (pintype "passive"))
      (node (ref "C48") (pin "1") (pintype "passive"))
      (node (ref "C49") (pin "1") (pintype "passive"))
      (node (ref "C5") (pin "1") (pintype "passive"))
      (node (ref "C50") (pin "2") (pintype "passive"))
      (node (ref "C51") (pin "2") (pintype "passive"))
      (node (ref "C55") (pin "1") (pintype "passive"))
      (node (ref "C56") (pin "1") (pintype "passive"))
      (node (ref "C57") (pin "2") (pintype "passive"))
      (node (ref "C6") (pin "1") (pintype "passive"))
      (node (ref "C9") (pin "1") (pintype "passive"))
      (node (ref "FPC") (pin "16") (pinfunction "16_16") (pintype "passive"))
      (node (ref "FPC") (pin "34") (pinfunction "34_34") (pintype "passive"))
      (node (ref "FPC") (pin "35") (pinfunction "35_35") (pintype "passive"))
      (node (ref "FPC") (pin "36") (pinfunction "36_36") (pintype "passive"))
      (node (ref "FPC") (pin "37") (pinfunction "37_37") (pintype "passive"))
      (node (ref "FPC") (pin "38") (pinfunction "38_38") (pintype "passive"))
      (node (ref "FPC") (pin "39") (pinfunction "39_39") (pintype "passive"))
      (node (ref "FPC") (pin "40") (pinfunction "40_40") (pintype "passive"))
      (node (ref "FPC") (pin "5") (pinfunction "5_5") (pintype "passive"))
      (node (ref "M") (pin "J1_1") (pinfunction "GND_J1_1") (pintype "passive"))
      (node (ref "M") (pin "J1_30") (pinfunction "GND_J1_30") (pintype "passive"))
      (node (ref "M") (pin "J2_31") (pinfunction "GND_J2_31") (pintype "passive"))
      (node (ref "M1") (pin "15") (pinfunction "DGND_15") (pintype "passive"))
      (node (ref "M1") (pin "2") (pinfunction "AGND_2") (pintype "passive"))
      (node (ref "M1") (pin "23") (pinfunction "AF-GND_23") (pintype "passive"))
      (node (ref "M1") (pin "25") (pinfunction "DGND_25") (pintype "passive"))
      (node (ref "M1") (pin "26") (pinfunction "DGND_26") (pintype "passive"))
      (node (ref "MOS1") (pin "2") (pinfunction "S_2") (pintype "passive"))
      (node (ref "P10") (pin "1") (pinfunction "1_1") (pintype "passive"))
      (node (ref "R11") (pin "2") (pintype "passive"))
      (node (ref "R12") (pin "2") (pintype "passive"))
      (node (ref "R13") (pin "2") (pintype "passive"))
      (node (ref "R41") (pin "1") (pintype "passive"))
      (node (ref "R44") (pin "1") (pintype "passive"))
      (node (ref "R45") (pin "1") (pintype "passive"))
      (node (ref "RST") (pin "2") (pinfunction "2_2") (pintype "passive"))
      (node (ref "TF_CARD") (pin "6") (pinfunction "VSS_6") (pintype "passive"))
      (node (ref "U12") (pin "1") (pinfunction "GND_1") (pintype "passive"))
      (node (ref "U14") (pin "1") (pinfunction "GND_1") (pintype "passive"))
      (node (ref "U2") (pin "12") (pinfunction "DGND_12") (pintype "passive"))
      (node (ref "U2") (pin "24") (pinfunction "SPKGND_24") (pintype "passive"))
      (node (ref "U2") (pin "33") (pinfunction "GNDPAD_33") (pintype "passive"))
      (node (ref "U5") (pin "1") (pinfunction "GND_1") (pintype "passive"))
      (node (ref "U6") (pin "3") (pinfunction "NC_3") (pintype "passive"))
      (node (ref "U6") (pin "4") (pinfunction "GND_4") (pintype "passive"))
      (node (ref "U7") (pin "6") (pinfunction "GND_6") (pintype "passive"))
      (node (ref "U7") (pin "7") (pinfunction "IN3_7") (pintype "passive"))
      (node (ref "U7") (pin "8") (pinfunction "IN4_8") (pintype "passive"))
      (node (ref "U8") (pin "1") (pinfunction "GND_1") (pintype "passive"))
      (node (ref "U9") (pin "1") (pinfunction "GND_1") (pintype "passive"))
      (node (ref "USB_232") (pin "5") (pinfunction "GND_5") (pintype "passive"))
      (node (ref "USB_SLAVE") (pin "5") (pinfunction "GND_5") (pintype "passive"))
      (node (ref "Y5") (pin "2") (pinfunction "GND_2") (pintype "passive"))
    )
    (net (code "131") (name "Net-(AUX_IN-CHL)") (class "Default")
      (node (ref "AUX_IN") (pin "1") (pinfunction "CHL_1") (pintype "passive"))
      (node (ref "C63") (pin "2") (pintype "passive"))
    )
    (net (code "132") (name "Net-(AUX_IN-CHR)") (class "Default")
      (node (ref "AUX_IN") (pin "2") (pinfunction "CHR_2") (pintype "passive"))
      (node (ref "C62") (pin "2") (pintype "passive"))
    )
    (net (code "133") (name "Net-(BAT-VCC)") (class "Default")
      (node (ref "BAT") (pin "1") (pinfunction "VCC_1") (pintype "passive"))
      (node (ref "D2") (pin "1") (pintype "passive"))
    )
    (net (code "134") (name "Net-(C52-GND)") (class "Default")
      (node (ref "C52") (pin "2") (pinfunction "GND_2") (pintype "passive"))
      (node (ref "RE") (pin "1") (pinfunction "1_1") (pintype "passive"))
    )
    (net (code "135") (name "Net-(C52-VCC)") (class "Default")
      (node (ref "C52") (pin "1") (pinfunction "VCC_1") (pintype "passive"))
      (node (ref "U2") (pin "29") (pinfunction "ROUT1_29") (pintype "passive"))
    )
    (net (code "136") (name "Net-(C53-GND)") (class "Default")
      (node (ref "C53") (pin "2") (pinfunction "GND_2") (pintype "passive"))
      (node (ref "LE") (pin "1") (pinfunction "1_1") (pintype "passive"))
    )
    (net (code "137") (name "Net-(C53-VCC)") (class "Default")
      (node (ref "C53") (pin "1") (pinfunction "VCC_1") (pintype "passive"))
      (node (ref "U2") (pin "30") (pinfunction "LOUT1_30") (pintype "passive"))
    )
    (net (code "138") (name "Net-(C66-Pad2)") (class "Default")
      (node (ref "C66") (pin "2") (pintype "passive"))
      (node (ref "C67") (pin "2") (pintype "passive"))
      (node (ref "PH") (pin "1") (pinfunction "1_1") (pintype "passive"))
    )
    (net (code "139") (name "Net-(MIC-GND)") (class "Default")
      (node (ref "C59") (pin "2") (pintype "passive"))
      (node (ref "C61") (pin "2") (pintype "passive"))
      (node (ref "MIC") (pin "2") (pinfunction "GND_2") (pintype "passive"))
      (node (ref "R48") (pin "2") (pintype "passive"))
    )
    (net (code "140") (name "Net-(MIC-VCC)") (class "Default")
      (node (ref "C58") (pin "2") (pintype "passive"))
      (node (ref "C60") (pin "2") (pintype "passive"))
      (node (ref "MIC") (pin "1") (pinfunction "VCC_1") (pintype "passive"))
      (node (ref "R46") (pin "2") (pintype "passive"))
      (node (ref "R47") (pin "2") (pintype "passive"))
      (node (ref "R66") (pin "2") (pintype "passive"))
    )
    (net (code "141") (name "Net-(MOS1-D)") (class "Default")
      (node (ref "LED5") (pin "2") (pinfunction "2_2") (pintype "passive"))
      (node (ref "MOS1") (pin "3") (pinfunction "D_3") (pintype "passive"))
    )
    (net (code "142") (name "Net-(U2-AUXL)") (class "Default")
      (node (ref "C62") (pin "1") (pintype "passive"))
      (node (ref "U2") (pin "19") (pinfunction "AUXL_19") (pintype "passive"))
    )
    (net (code "143") (name "Net-(U2-AUXR)") (class "Default")
      (node (ref "C63") (pin "1") (pintype "passive"))
      (node (ref "U2") (pin "20") (pinfunction "AUXR_20") (pintype "passive"))
    )
    (net (code "144") (name "Net-(U2-DBVDD)") (class "Default")
      (node (ref "C48") (pin "2") (pintype "passive"))
      (node (ref "C49") (pin "2") (pintype "passive"))
      (node (ref "R43") (pin "2") (pintype "passive"))
      (node (ref "U2") (pin "13") (pinfunction "DCVDD_13") (pintype "passive"))
      (node (ref "U2") (pin "14") (pinfunction "DBVDD_14") (pintype "passive"))
    )
    (net (code "145") (name "Net-(U2-L2{slash}GPIO2)") (class "Default")
      (node (ref "C66") (pin "1") (pintype "passive"))
      (node (ref "U2") (pin "3") (pinfunction "L2/GPIO2_3") (pintype "passive"))
    )
    (net (code "146") (name "Net-(U2-LIN)") (class "Default")
      (node (ref "C59") (pin "1") (pintype "passive"))
      (node (ref "U2") (pin "2") (pinfunction "LIN_2") (pintype "passive"))
    )
    (net (code "147") (name "Net-(U2-LIP)") (class "Default")
      (node (ref "C58") (pin "1") (pintype "passive"))
      (node (ref "U2") (pin "1") (pinfunction "LIP_1") (pintype "passive"))
    )
    (net (code "148") (name "Net-(U2-LOUT2)") (class "Default")
      (node (ref "SPK+") (pin "1") (pinfunction "1_1") (pintype "passive"))
      (node (ref "U2") (pin "25") (pinfunction "LOUT2_25") (pintype "passive"))
    )
    (net (code "149") (name "Net-(U2-MICBIAS)") (class "Default")
      (node (ref "C65") (pin "2") (pintype "passive"))
      (node (ref "R46") (pin "1") (pintype "passive"))
      (node (ref "U2") (pin "32") (pinfunction "MICBIAS_32") (pintype "passive"))
    )
    (net (code "150") (name "Net-(U2-MODE)") (class "Default")
      (node (ref "R45") (pin "2") (pintype "passive"))
      (node (ref "U2") (pin "18") (pinfunction "MODE_18") (pintype "passive"))
    )
    (net (code "151") (name "Net-(U2-R2{slash}GPIO3)") (class "Default")
      (node (ref "C67") (pin "1") (pintype "passive"))
      (node (ref "U2") (pin "6") (pinfunction "R2/GPIO3_6") (pintype "passive"))
    )
    (net (code "152") (name "Net-(U2-RIN)") (class "Default")
      (node (ref "C61") (pin "1") (pintype "passive"))
      (node (ref "U2") (pin "5") (pinfunction "RIN_5") (pintype "passive"))
    )
    (net (code "153") (name "Net-(U2-RIP)") (class "Default")
      (node (ref "C60") (pin "1") (pintype "passive"))
      (node (ref "U2") (pin "4") (pinfunction "RIP_4") (pintype "passive"))
    )
    (net (code "154") (name "Net-(U2-ROUT2)") (class "Default")
      (node (ref "SPK-") (pin "1") (pinfunction "1_1") (pintype "passive"))
      (node (ref "U2") (pin "23") (pinfunction "ROUT2_23") (pintype "passive"))
    )
    (net (code "155") (name "Net-(U2-SPKVDD)") (class "Default")
      (node (ref "C46") (pin "2") (pintype "passive"))
      (node (ref "C47") (pin "2") (pintype "passive"))
      (node (ref "R42") (pin "1") (pintype "passive"))
      (node (ref "U2") (pin "26") (pinfunction "SPKVDD_26") (pintype "passive"))
    )
    (net (code "156") (name "Net-(U2-VMID)") (class "Default")
      (node (ref "C64") (pin "2") (pintype "passive"))
      (node (ref "U2") (pin "27") (pinfunction "VMID_27") (pintype "passive"))
    )
    (net (code "157") (name "Net-(U5-VIN)") (class "Default")
      (node (ref "C38") (pin "2") (pintype "passive"))
      (node (ref "L5") (pin "2") (pintype "passive"))
      (node (ref "U5") (pin "3") (pinfunction "VIN_3") (pintype "passive"))
    )
    (net (code "158") (name "Net-(U5-VOUT)") (class "Default")
      (node (ref "L6") (pin "1") (pintype "passive"))
      (node (ref "U5") (pin "2") (pinfunction "VOUT_2") (pintype "passive"))
    )
    (net (code "159") (name "Net-(U12-IN)") (class "Default")
      (node (ref "C45") (pin "2") (pintype "passive"))
      (node (ref "P1") (pin "1") (pinfunction "1_1") (pintype "passive"))
      (node (ref "U12") (pin "3") (pinfunction "IN_3") (pintype "passive"))
    )
    (net (code "160") (name "Net-(U14-D+)") (class "Default")
      (node (ref "U14") (pin "5") (pinfunction "D+_5") (pintype "passive"))
      (node (ref "USB_232") (pin "3") (pinfunction "D+_3") (pintype "passive"))
    )
    (net (code "161") (name "Net-(U14-D-)") (class "Default")
      (node (ref "U14") (pin "6") (pinfunction "D-_6") (pintype "passive"))
      (node (ref "USB_232") (pin "2") (pinfunction "D-_2") (pintype "passive"))
    )
    (net (code "162") (name "Net-(U14-V3)") (class "Default")
      (node (ref "C55") (pin "2") (pintype "passive"))
      (node (ref "U14") (pin "4") (pinfunction "V3_4") (pintype "passive"))
    )
    (net (code "163") (name "Net-(U14-XI)") (class "Default")
      (node (ref "C56") (pin "2") (pintype "passive"))
      (node (ref "U14") (pin "7") (pinfunction "XI_7") (pintype "passive"))
      (node (ref "Y3") (pin "1") (pinfunction "OSC1_1") (pintype "passive"))
    )
    (net (code "164") (name "Net-(U14-XO)") (class "Default")
      (node (ref "C57") (pin "1") (pintype "passive"))
      (node (ref "U14") (pin "8") (pinfunction "XO_8") (pintype "passive"))
      (node (ref "Y3") (pin "2") (pinfunction "OSC2_2") (pintype "passive"))
    )
    (net (code "165") (name "Net-(USB_SLAVE-D+)") (class "Default")
      (node (ref "R32") (pin "1") (pintype "passive"))
      (node (ref "R35") (pin "1") (pintype "passive"))
      (node (ref "USB_SLAVE") (pin "3") (pinfunction "D+_3") (pintype "passive"))
    )
    (net (code "166") (name "Net-(USB_SLAVE-D-)") (class "Default")
      (node (ref "R33") (pin "1") (pintype "passive"))
      (node (ref "USB_SLAVE") (pin "2") (pinfunction "D-_2") (pintype "passive"))
    )
    (net (code "167") (name "Net-(Y5-VCC)") (class "Default")
      (node (ref "C23") (pin "2") (pintype "passive"))
      (node (ref "L2") (pin "1") (pintype "passive"))
      (node (ref "Y5") (pin "4") (pinfunction "VCC_4") (pintype "passive"))
    )
    (net (code "168") (name "VCC1.5") (class "Default")
      (node (ref "C22") (pin "1") (pintype "passive"))
      (node (ref "C39") (pin "2") (pintype "passive"))
      (node (ref "C40") (pin "2") (pintype "passive"))
      (node (ref "L6") (pin "2") (pintype "passive"))
      (node (ref "M1") (pin "10") (pinfunction "DVDD_10") (pintype "passive"))
    )
    (net (code "169") (name "VCC2.8") (class "Default")
      (node (ref "C28") (pin "2") (pintype "passive"))
      (node (ref "C30") (pin "2") (pintype "passive"))
      (node (ref "L3") (pin "2") (pintype "passive"))
      (node (ref "L4") (pin "2") (pintype "passive"))
      (node (ref "L5") (pin "1") (pintype "passive"))
      (node (ref "U9") (pin "2") (pinfunction "VOUT_2") (pintype "passive"))
    )
    (net (code "170") (name "VCC3.3") (class "Default")
      (node (ref "C32") (pin "2") (pintype "passive"))
      (node (ref "C33") (pin "2") (pintype "passive"))
      (node (ref "C35") (pin "2") (pintype "passive"))
      (node (ref "C36") (pin "1") (pintype "passive"))
      (node (ref "C41") (pin "1") (pintype "passive"))
      (node (ref "C42") (pin "1") (pintype "passive"))
      (node (ref "C43") (pin "2") (pintype "passive"))
      (node (ref "C44") (pin "1") (pinfunction "VCC_1") (pintype "passive"))
      (node (ref "FPC") (pin "33") (pinfunction "33_33") (pintype "passive"))
      (node (ref "FPC") (pin "6") (pinfunction "6_6") (pintype "passive"))
      (node (ref "FPC") (pin "7") (pinfunction "7_7") (pintype "passive"))
      (node (ref "L2") (pin "2") (pintype "passive"))
      (node (ref "LED5") (pin "1") (pinfunction "1_1") (pintype "passive"))
      (node (ref "R18") (pin "2") (pintype "passive"))
      (node (ref "R21") (pin "2") (pintype "passive"))
      (node (ref "R23") (pin "2") (pintype "passive"))
      (node (ref "R27") (pin "1") (pintype "passive"))
      (node (ref "R28") (pin "2") (pintype "passive"))
      (node (ref "R29") (pin "2") (pintype "passive"))
      (node (ref "R35") (pin "2") (pintype "passive"))
      (node (ref "R4") (pin "2") (pintype "passive"))
      (node (ref "R43") (pin "1") (pintype "passive"))
      (node (ref "R5") (pin "2") (pintype "passive"))
      (node (ref "R6") (pin "2") (pintype "passive"))
      (node (ref "R74") (pin "2") (pintype "passive"))
      (node (ref "TF_CARD") (pin "4") (pinfunction "VDD_4") (pintype "passive"))
      (node (ref "U12") (pin "2") (pinfunction "OUT_2") (pintype "passive"))
      (node (ref "U12") (pin "4") (pinfunction "OUT_4") (pintype "passive"))
      (node (ref "U2") (pin "31") (pinfunction "AVDD_31") (pintype "passive"))
      (node (ref "U6") (pin "1") (pinfunction "VCC_1") (pintype "passive"))
      (node (ref "U8") (pin "3") (pinfunction "VIN_3") (pintype "passive"))
      (node (ref "U9") (pin "3") (pinfunction "VIN_3") (pintype "passive"))
    )
    (net (code "171") (name "VCC3.3M") (class "Default")
      (node (ref "D1") (pin "1") (pintype "passive"))
      (node (ref "R2") (pin "2") (pintype "passive"))
    )
    (net (code "172") (name "VCC5") (class "Default")
      (node (ref "C50") (pin "1") (pintype "passive"))
      (node (ref "C51") (pin "1") (pintype "passive"))
      (node (ref "M") (pin "J1_58") (pinfunction "VCC5_J1_58") (pintype "passive"))
      (node (ref "M") (pin "J1_59") (pinfunction "VCC5_J1_59") (pintype "passive"))
      (node (ref "M") (pin "J1_60") (pinfunction "VCC5_J1_60") (pintype "passive"))
      (node (ref "P1") (pin "2") (pinfunction "2_2") (pintype "passive"))
      (node (ref "R42") (pin "2") (pintype "passive"))
      (node (ref "U14") (pin "16") (pinfunction "VCC_16") (pintype "passive"))
      (node (ref "USB_232") (pin "1") (pinfunction "VCC_1") (pintype "passive"))
      (node (ref "USB_SLAVE") (pin "1") (pinfunction "VCC_1") (pintype "passive"))
    )
    (net (code "173") (name "unconnected-(FPC-Pad8)") (class "Default")
      (node (ref "FPC") (pin "8") (pinfunction "8_8") (pintype "passive"))
    )
    (net (code "174") (name "unconnected-(FPC-Pad13)") (class "Default")
      (node (ref "FPC") (pin "13") (pinfunction "13_13") (pintype "passive"))
    )
    (net (code "175") (name "unconnected-(FPC-Pad14)") (class "Default")
      (node (ref "FPC") (pin "14") (pinfunction "14_14") (pintype "passive"))
    )
    (net (code "176") (name "unconnected-(FPC-PadA)") (class "Default")
      (node (ref "FPC") (pin "A") (pinfunction "A_A") (pintype "passive"))
    )
    (net (code "177") (name "unconnected-(FPC-PadB)") (class "Default")
      (node (ref "FPC") (pin "B") (pinfunction "B_B") (pintype "passive"))
    )
    (net (code "178") (name "unconnected-(GE-Pad1)") (class "Default")
      (node (ref "GE") (pin "1") (pinfunction "1_1") (pintype "passive"))
    )
    (net (code "179") (name "unconnected-(LI-Pad1)") (class "Default")
      (node (ref "LI") (pin "1") (pinfunction "1_1") (pintype "passive"))
    )
    (net (code "180") (name "unconnected-(M1-NC-Pad27)") (class "Default")
      (node (ref "M1") (pin "27") (pinfunction "NC_27") (pintype "passive+no_connect"))
    )
    (net (code "181") (name "unconnected-(RI-Pad1)") (class "Default")
      (node (ref "RI") (pin "1") (pinfunction "1_1") (pintype "passive"))
    )
    (net (code "182") (name "unconnected-(TFTLCD-BL-Pad23)") (class "Default")
      (node (ref "TFTLCD") (pin "23") (pinfunction "BL_23") (pintype "passive"))
    )
    (net (code "183") (name "unconnected-(TFTLCD-BL_VDD-Pad28)") (class "Default")
      (node (ref "TFTLCD") (pin "28") (pinfunction "BL_VDD_28") (pintype "passive"))
    )
    (net (code "184") (name "unconnected-(TFTLCD-GND-Pad22)") (class "Default")
      (node (ref "TFTLCD") (pin "22") (pinfunction "GND_22") (pintype "passive"))
    )
    (net (code "185") (name "unconnected-(TFTLCD-GND-Pad26)") (class "Default")
      (node (ref "TFTLCD") (pin "26") (pinfunction "GND_26") (pintype "passive"))
    )
    (net (code "186") (name "unconnected-(TFTLCD-GND-Pad27)") (class "Default")
      (node (ref "TFTLCD") (pin "27") (pinfunction "GND_27") (pintype "passive"))
    )
    (net (code "187") (name "unconnected-(TFTLCD-MO-Pad32)") (class "Default")
      (node (ref "TFTLCD") (pin "32") (pinfunction "MO_32") (pintype "passive"))
    )
    (net (code "188") (name "unconnected-(TFTLCD-VDD3.3-Pad24)") (class "Default")
      (node (ref "TFTLCD") (pin "24") (pinfunction "VDD3.3_24") (pintype "passive"))
    )
    (net (code "189") (name "unconnected-(TFTLCD-VDD3.3-Pad25)") (class "Default")
      (node (ref "TFTLCD") (pin "25") (pinfunction "VDD3.3_25") (pintype "passive"))
    )
    (net (code "190") (name "unconnected-(U2-CSB{slash}GPIO1-Pad15)") (class "Default")
      (node (ref "U2") (pin "15") (pinfunction "CSB/GPIO1_15") (pintype "passive"))
    )
    (net (code "191") (name "unconnected-(U2-OUT3-Pad22)") (class "Default")
      (node (ref "U2") (pin "22") (pinfunction "OUT3_22") (pintype "passive"))
    )
    (net (code "192") (name "unconnected-(U2-OUT4-Pad21)") (class "Default")
      (node (ref "U2") (pin "21") (pinfunction "OUT4_21") (pintype "passive"))
    )
    (net (code "193") (name "unconnected-(U14-CTS#-Pad9)") (class "Default")
      (node (ref "U14") (pin "9") (pinfunction "CTS#_9") (pintype "passive"))
    )
    (net (code "194") (name "unconnected-(U14-DCD#-Pad12)") (class "Default")
      (node (ref "U14") (pin "12") (pinfunction "DCD#_12") (pintype "passive"))
    )
    (net (code "195") (name "unconnected-(U14-DSR#-Pad10)") (class "Default")
      (node (ref "U14") (pin "10") (pinfunction "DSR#_10") (pintype "passive"))
    )
    (net (code "196") (name "unconnected-(U14-DTR#-Pad13)") (class "Default")
      (node (ref "U14") (pin "13") (pinfunction "DTR#_13") (pintype "passive"))
    )
    (net (code "197") (name "unconnected-(U14-R232-Pad15)") (class "Default")
      (node (ref "U14") (pin "15") (pinfunction "R232_15") (pintype "passive"))
    )
    (net (code "198") (name "unconnected-(U14-RI#-Pad11)") (class "Default")
      (node (ref "U14") (pin "11") (pinfunction "RI#_11") (pintype "passive"))
    )
    (net (code "199") (name "unconnected-(U14-RTS#-Pad14)") (class "Default")
      (node (ref "U14") (pin "14") (pinfunction "RTS#_14") (pintype "passive"))
    )
    (net (code "200") (name "unconnected-(USB_232-NC-Pad4)") (class "Default")
      (node (ref "USB_232") (pin "4") (pinfunction "NC_4") (pintype "passive"))
    )
    (net (code "201") (name "unconnected-(USB_SLAVE-NC-Pad4)") (class "Default")
      (node (ref "USB_SLAVE") (pin "4") (pinfunction "NC_4") (pintype "passive"))
    )
    (net (code "202") (name "unconnected-(Y5-NC-Pad1)") (class "Default")
      (node (ref "Y5") (pin "1") (pinfunction "NC_1") (pintype "passive"))
    )
  )
)
